# Peripherals.net
KiCad netlist of a schematic drawn in Altium Designer
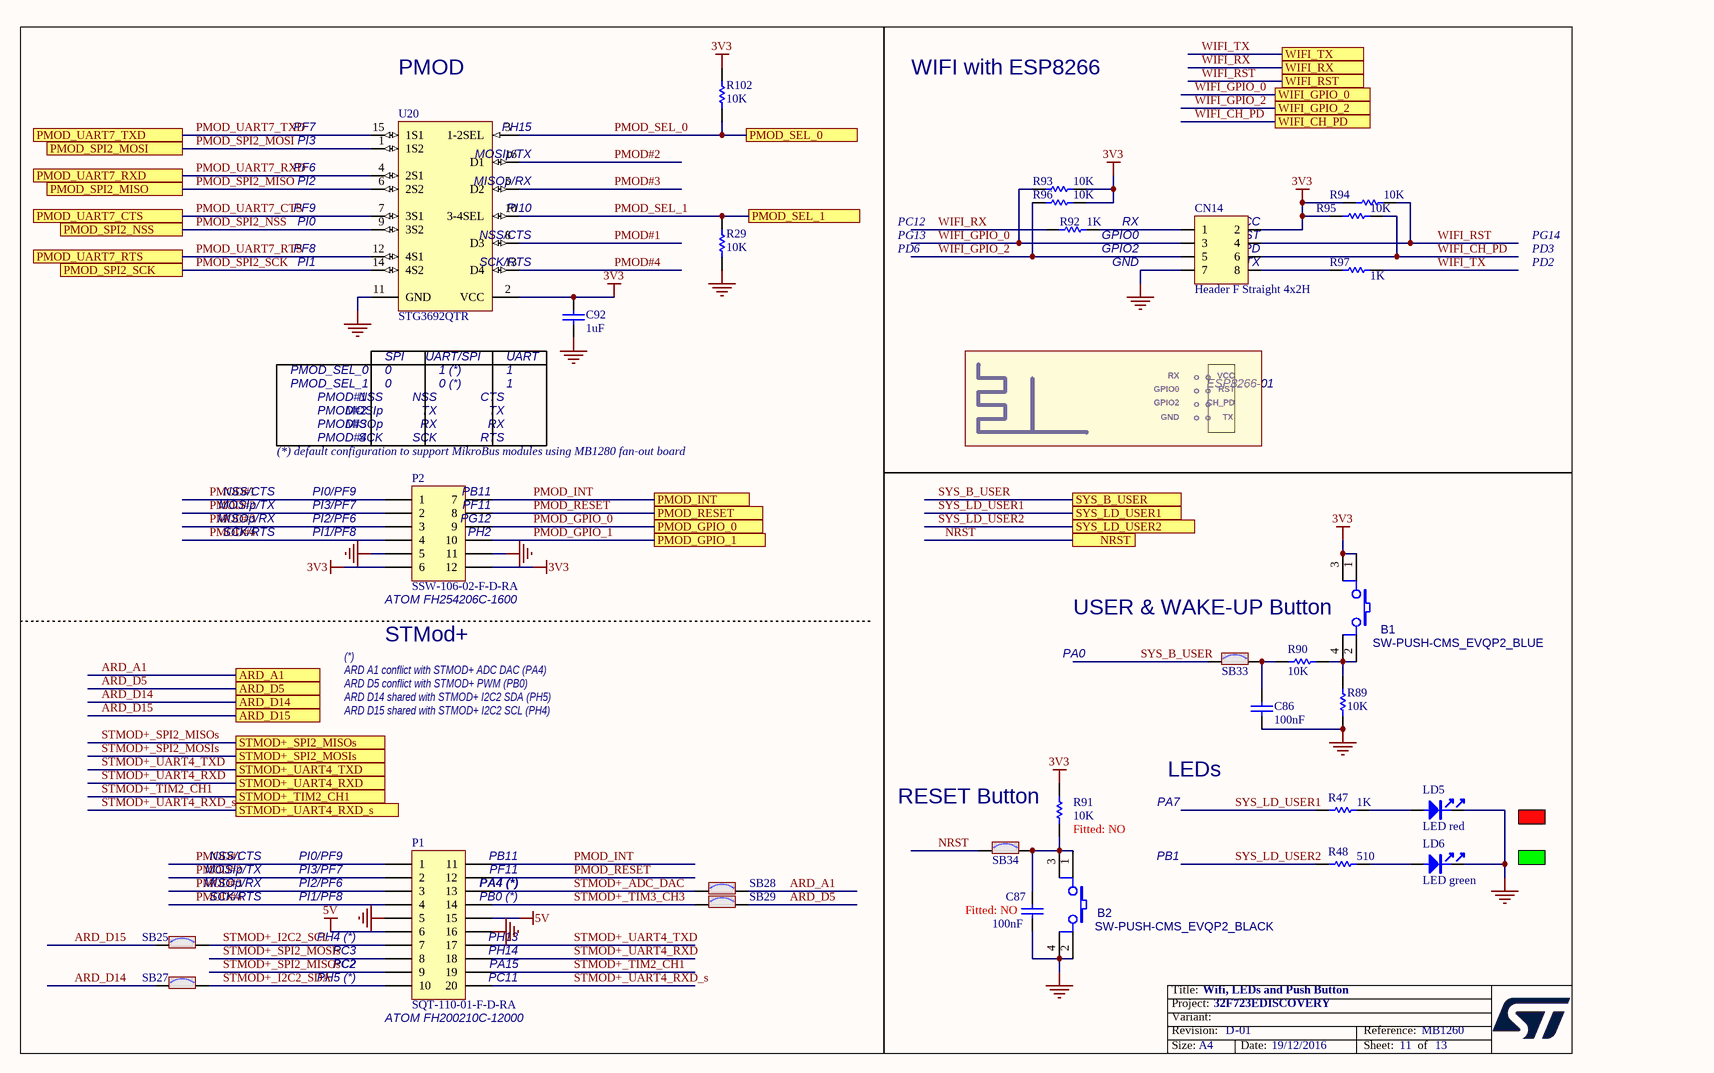
[diagram p0: Peripherals.SchDoc]

(export (version "E")
  (design (tool "Eeschema 10.0.6"))
  (components
    (comp (ref "B1")
      (value "SW-PUSH-CMS_EVQP2_BLUE")
      (footprint "TACT_4SM_3R5X5R5")
      (description "EVQP2 - 4.7mm x 3.5 mm SMD Light Touch Switch")
      (libsource (lib "MCD_TEMP_NPA") (part "SW-PUSH-CMS_EVQP2_BLUE"))
    )
    (comp (ref "B2")
      (value "SW-PUSH-CMS_EVQP2_BLACK")
      (footprint "TACT_4SM_3R5X5R5")
      (description "EVQP2 - 4.7mm x 3.5 mm SMD Light Touch Switch")
      (libsource (lib "MCD_TEMP_NPA") (part "SW-PUSH-CMS_EVQP2_BLACK"))
    )
    (comp (ref "C86")
      (value "100nF")
      (footprint "0402C")
      (description "Capacitor,100nF,16V,X7R,10%,0402,YAGEO")
      (libsource (lib "MCD_TOOLS") (part "Cap_100nF_X7R_10%_0402"))
    )
    (comp (ref "C87")
      (value "100nF")
      (footprint "0402C")
      (description "Capacitor,100nF,16V,X7R,10%,0402,YAGEO")
      (fields (field (name "FITTED") "NO"))
      (libsource (lib "MCD_TOOLS") (part "Cap_100nF_X7R_10%_0402"))
    )
    (comp (ref "C92")
      (value "1uF")
      (footprint "0603C")
      (description "Capacitor,1uF,16V,X5R,10%,0603,YAGEO")
      (libsource (lib "MCD_TOOLS_CAPACITOR") (part "Cap_1uF_X5R_10%_0603"))
    )
    (comp (ref "CN14")
      (value "Header F Straight 4x2H")
      (footprint "HDR_2X4_2R54")
      (description "Header Female, 4-Pin, Dual row, Straight")
      (libsource (lib "MCD_TOOLS_CONNECTOR") (part "Header 4X2F"))
    )
    (comp (ref "LD5")
      (value "LED red")
      (footprint "0603D")
      (description "LED red 0603")
      (libsource (lib "MCD_TEMP_NPA") (part "LED_red"))
    )
    (comp (ref "LD6")
      (value "LED green")
      (footprint "0603D")
      (description "LED green 0603")
      (libsource (lib "MCD_TEMP_NPA") (part "LED_green"))
    )
    (comp (ref "P1")
      (value "SQT-110-01-F-D-RA")
      (footprint "SQT-110-01-F-D-RA")
      (description "20 Position Receptacle Connector 0.079\" (2.00mm) Through Hole Right Angle")
      (libsource (lib "MCD_TEMP_NPA") (part "Header 10X2 TH RA 2mm"))
    )
    (comp (ref "P2")
      (value "SSW-106-02-F-D-RA")
      (footprint "SSW-106-02-F-D-RA")
      (description "12 Position Receptacle Connector 0.100\" (2.54mm) Through Hole Right Angle")
      (libsource (lib "MCD_TEMP_NPA") (part "Header 6X2 TH RA 2.54mm"))
    )
    (comp (ref "R29")
      (value "10K")
      (footprint "0402R")
      (description "Resistor,10K,0402,1%,YAGEO")
      (libsource (lib "MCD_TOOLS") (part "Res_10K_1%_0402"))
    )
    (comp (ref "R47")
      (value "1K")
      (footprint "0603R")
      (description "Resistor,1K,0603,1%,YAGEO")
      (fields (field (name "Comment") "1K_1%_0603"))
      (libsource (lib "MCD_TOOLS_RESISTOR") (part "Res_1K_1%_0603"))
    )
    (comp (ref "R48")
      (value "510")
      (footprint "0603R")
      (description "Resistor,510,0603,1%,YAGEO")
      (fields (field (name "Comment") "510_1%_0603"))
      (libsource (lib "MCD_TEMP_NPA") (part "Res_510_1%_0603"))
    )
    (comp (ref "R89")
      (value "10K")
      (footprint "0402R")
      (description "Resistor,10K,0402,1%,YAGEO")
      (libsource (lib "MCD_TOOLS") (part "Res_10K_1%_0402"))
    )
    (comp (ref "R90")
      (value "10K")
      (footprint "0402R")
      (description "Resistor,10K,0402,1%,YAGEO")
      (libsource (lib "MCD_TOOLS") (part "Res_10K_1%_0402"))
    )
    (comp (ref "R91")
      (value "10K")
      (footprint "0402R")
      (description "Resistor,10K,0402,1%,YAGEO")
      (fields (field (name "FITTED") "NO"))
      (libsource (lib "MCD_TOOLS") (part "Res_10K_1%_0402"))
    )
    (comp (ref "R92")
      (value "1K")
      (footprint "0402R")
      (description "Resistor,1K,0402,1%,YAGEO")
      (libsource (lib "MCD_TOOLS_RESISTOR") (part "Res_1K_1%_0402"))
    )
    (comp (ref "R93")
      (value "10K")
      (footprint "0402R")
      (description "Resistor,10K,0402,1%,YAGEO")
      (libsource (lib "MCD_TOOLS") (part "Res_10K_1%_0402"))
    )
    (comp (ref "R94")
      (value "10K")
      (footprint "0402R")
      (description "Resistor,10K,0402,1%,YAGEO")
      (libsource (lib "MCD_TOOLS") (part "Res_10K_1%_0402"))
    )
    (comp (ref "R95")
      (value "10K")
      (footprint "0402R")
      (description "Resistor,10K,0402,1%,YAGEO")
      (libsource (lib "MCD_TOOLS") (part "Res_10K_1%_0402"))
    )
    (comp (ref "R96")
      (value "10K")
      (footprint "0402R")
      (description "Resistor,10K,0402,1%,YAGEO")
      (libsource (lib "MCD_TOOLS") (part "Res_10K_1%_0402"))
    )
    (comp (ref "R97")
      (value "1K")
      (footprint "0402R")
      (description "Resistor,1K,0402,1%,YAGEO")
      (libsource (lib "MCD_TOOLS_RESISTOR") (part "Res_1K_1%_0402"))
    )
    (comp (ref "R102")
      (value "10K")
      (footprint "0402R")
      (description "Resistor,10K,0402,1%,YAGEO")
      (libsource (lib "MCD_TOOLS") (part "Res_10K_1%_0402"))
    )
    (comp (ref "SB25")
      (value "Solder Bridge ON")
      (footprint "JP2_SMD")
      (libsource (lib "MCD_TOOLS") (part "SB_ON"))
    )
    (comp (ref "SB27")
      (value "Solder Bridge ON")
      (footprint "JP2_SMD")
      (libsource (lib "MCD_TOOLS") (part "SB_ON"))
    )
    (comp (ref "SB28")
      (value "Solder Bridge ON")
      (footprint "JP2_SMD")
      (libsource (lib "MCD_TOOLS") (part "SB_ON"))
    )
    (comp (ref "SB29")
      (value "Solder Bridge ON")
      (footprint "JP2_SMD")
      (libsource (lib "MCD_TOOLS") (part "SB_ON"))
    )
    (comp (ref "SB33")
      (value "Solder Bridge ON")
      (footprint "JP2_SMD")
      (libsource (lib "MCD_TOOLS") (part "SB_ON"))
    )
    (comp (ref "SB34")
      (value "Solder Bridge ON")
      (footprint "JP2_SMD")
      (libsource (lib "MCD_TOOLS") (part "SB_ON"))
    )
    (comp (ref "U20")
      (value "STG3692QTR")
      (footprint "QFN16_0R4_2R5X1R7")
      (description "Low voltage high bandwidth quad SPDT switch")
      (libsource (lib "MCD_TEMP_NPA") (part "STG3692QTR"))
    )
  )
  (nets
    (net (code "1") (name "/ARD_A1") (class "Default")
      (node (ref "SB28") (pin "2") (pinfunction "2_2") (pintype "passive"))
    )
    (net (code "2") (name "/ARD_D5") (class "Default")
      (node (ref "SB29") (pin "2") (pinfunction "2_2") (pintype "passive"))
    )
    (net (code "3") (name "/ARD_D14") (class "Default")
      (node (ref "SB27") (pin "1") (pinfunction "1_1") (pintype "passive"))
    )
    (net (code "4") (name "/ARD_D15") (class "Default")
      (node (ref "SB25") (pin "1") (pinfunction "1_1") (pintype "passive"))
    )
    (net (code "5") (name "/NRST") (class "Default")
      (node (ref "SB34") (pin "1") (pinfunction "1_1") (pintype "passive"))
    )
    (net (code "6") (name "/PMOD#1") (class "Default")
      (node (ref "P1") (pin "1") (pinfunction "1_1") (pintype "passive"))
      (node (ref "P2") (pin "1") (pinfunction "1_1") (pintype "passive"))
      (node (ref "U20") (pin "8") (pinfunction "D3_8") (pintype "bidirectional"))
    )
    (net (code "7") (name "/PMOD#2") (class "Default")
      (node (ref "P1") (pin "2") (pinfunction "2_2") (pintype "passive"))
      (node (ref "P2") (pin "2") (pinfunction "2_2") (pintype "passive"))
      (node (ref "U20") (pin "16") (pinfunction "D1_16") (pintype "bidirectional"))
    )
    (net (code "8") (name "/PMOD#3") (class "Default")
      (node (ref "P1") (pin "3") (pinfunction "3_3") (pintype "passive"))
      (node (ref "P2") (pin "3") (pinfunction "3_3") (pintype "passive"))
      (node (ref "U20") (pin "5") (pinfunction "D2_5") (pintype "bidirectional"))
    )
    (net (code "9") (name "/PMOD#4") (class "Default")
      (node (ref "P1") (pin "4") (pinfunction "4_4") (pintype "passive"))
      (node (ref "P2") (pin "4") (pinfunction "4_4") (pintype "passive"))
      (node (ref "U20") (pin "13") (pinfunction "D4_13") (pintype "bidirectional"))
    )
    (net (code "10") (name "/PMOD_GPIO_0") (class "Default")
      (node (ref "P2") (pin "9") (pinfunction "9_9") (pintype "passive"))
    )
    (net (code "11") (name "/PMOD_GPIO_1") (class "Default")
      (node (ref "P2") (pin "10") (pinfunction "10_10") (pintype "passive"))
    )
    (net (code "12") (name "/PMOD_INT") (class "Default")
      (node (ref "P1") (pin "11") (pinfunction "11_11") (pintype "passive"))
      (node (ref "P2") (pin "7") (pinfunction "7_7") (pintype "passive"))
    )
    (net (code "13") (name "/PMOD_RESET") (class "Default")
      (node (ref "P1") (pin "12") (pinfunction "12_12") (pintype "passive"))
      (node (ref "P2") (pin "8") (pinfunction "8_8") (pintype "passive"))
    )
    (net (code "14") (name "/PMOD_SEL_0") (class "Default")
      (node (ref "R102") (pin "1") (pinfunction "1_1") (pintype "passive"))
      (node (ref "U20") (pin "3") (pinfunction "1-2SEL_3") (pintype "input"))
    )
    (net (code "15") (name "/PMOD_SEL_1") (class "Default")
      (node (ref "R29") (pin "2") (pinfunction "2_2") (pintype "passive"))
      (node (ref "U20") (pin "10") (pinfunction "3-4SEL_10") (pintype "bidirectional"))
    )
    (net (code "16") (name "/PMOD_SPI2_MISO") (class "Default")
      (node (ref "U20") (pin "6") (pinfunction "2S2_6") (pintype "bidirectional"))
    )
    (net (code "17") (name "/PMOD_SPI2_MOSI") (class "Default")
      (node (ref "U20") (pin "1") (pinfunction "1S2_1") (pintype "bidirectional"))
    )
    (net (code "18") (name "/PMOD_SPI2_NSS") (class "Default")
      (node (ref "U20") (pin "9") (pinfunction "3S2_9") (pintype "bidirectional"))
    )
    (net (code "19") (name "/PMOD_SPI2_SCK") (class "Default")
      (node (ref "U20") (pin "14") (pinfunction "4S2_14") (pintype "bidirectional"))
    )
    (net (code "20") (name "/PMOD_UART7_CTS") (class "Default")
      (node (ref "U20") (pin "7") (pinfunction "3S1_7") (pintype "bidirectional"))
    )
    (net (code "21") (name "/PMOD_UART7_RTS") (class "Default")
      (node (ref "U20") (pin "12") (pinfunction "4S1_12") (pintype "bidirectional"))
    )
    (net (code "22") (name "/PMOD_UART7_RXD") (class "Default")
      (node (ref "U20") (pin "4") (pinfunction "2S1_4") (pintype "bidirectional"))
    )
    (net (code "23") (name "/PMOD_UART7_TXD") (class "Default")
      (node (ref "U20") (pin "15") (pinfunction "1S1_15") (pintype "bidirectional"))
    )
    (net (code "24") (name "/STMOD+_ADC_DAC") (class "Default")
      (node (ref "P1") (pin "13") (pinfunction "13_13") (pintype "passive"))
      (node (ref "SB28") (pin "1") (pinfunction "1_1") (pintype "passive"))
    )
    (net (code "25") (name "/STMOD+_I2C2_SCL") (class "Default")
      (node (ref "P1") (pin "7") (pinfunction "7_7") (pintype "passive"))
      (node (ref "SB25") (pin "2") (pinfunction "2_2") (pintype "passive"))
    )
    (net (code "26") (name "/STMOD+_I2C2_SDA") (class "Default")
      (node (ref "P1") (pin "10") (pinfunction "10_10") (pintype "passive"))
      (node (ref "SB27") (pin "2") (pinfunction "2_2") (pintype "passive"))
    )
    (net (code "27") (name "/STMOD+_SPI2_MISOs") (class "Default")
      (node (ref "P1") (pin "9") (pinfunction "9_9") (pintype "passive"))
    )
    (net (code "28") (name "/STMOD+_SPI2_MOSIs") (class "Default")
      (node (ref "P1") (pin "8") (pinfunction "8_8") (pintype "passive"))
    )
    (net (code "29") (name "/STMOD+_TIM2_CH1") (class "Default")
      (node (ref "P1") (pin "19") (pinfunction "19_19") (pintype "passive"))
    )
    (net (code "30") (name "/STMOD+_TIM3_CH3") (class "Default")
      (node (ref "P1") (pin "14") (pinfunction "14_14") (pintype "passive"))
      (node (ref "SB29") (pin "1") (pinfunction "1_1") (pintype "passive"))
    )
    (net (code "31") (name "/STMOD+_UART4_RXD") (class "Default")
      (node (ref "P1") (pin "18") (pinfunction "18_18") (pintype "passive"))
    )
    (net (code "32") (name "/STMOD+_UART4_RXD_s") (class "Default")
      (node (ref "P1") (pin "20") (pinfunction "20_20") (pintype "passive"))
    )
    (net (code "33") (name "/STMOD+_UART4_TXD") (class "Default")
      (node (ref "P1") (pin "17") (pinfunction "17_17") (pintype "passive"))
    )
    (net (code "34") (name "/SYS_B_USER") (class "Default")
      (node (ref "SB33") (pin "1") (pinfunction "1_1") (pintype "passive"))
    )
    (net (code "35") (name "/SYS_LD_USER1") (class "Default")
      (node (ref "R47") (pin "1") (pinfunction "1_1") (pintype "passive"))
    )
    (net (code "36") (name "/SYS_LD_USER2") (class "Default")
      (node (ref "R48") (pin "1") (pinfunction "1_1") (pintype "passive"))
    )
    (net (code "37") (name "/WIFI_CH_PD") (class "Default")
      (node (ref "CN14") (pin "6") (pinfunction "6_6") (pintype "passive"))
      (node (ref "R95") (pin "2") (pinfunction "2_2") (pintype "passive"))
    )
    (net (code "38") (name "/WIFI_GPIO_0") (class "Default")
      (node (ref "CN14") (pin "3") (pinfunction "3_3") (pintype "passive"))
      (node (ref "R93") (pin "2") (pinfunction "2_2") (pintype "passive"))
    )
    (net (code "39") (name "/WIFI_GPIO_2") (class "Default")
      (node (ref "CN14") (pin "5") (pinfunction "5_5") (pintype "passive"))
      (node (ref "R96") (pin "2") (pinfunction "2_2") (pintype "passive"))
    )
    (net (code "40") (name "/WIFI_RST") (class "Default")
      (node (ref "CN14") (pin "4") (pinfunction "4_4") (pintype "passive"))
      (node (ref "R94") (pin "2") (pinfunction "2_2") (pintype "passive"))
    )
    (net (code "41") (name "/WIFI_RX") (class "Default")
      (node (ref "R92") (pin "1") (pinfunction "1_1") (pintype "passive"))
    )
    (net (code "42") (name "/WIFI_TX") (class "Default")
      (node (ref "R97") (pin "2") (pinfunction "2_2") (pintype "passive"))
    )
    (net (code "43") (name "3V3") (class "Default")
      (node (ref "B1") (pin "1") (pinfunction "1_1") (pintype "passive"))
      (node (ref "B1") (pin "3") (pinfunction "3_3") (pintype "passive"))
      (node (ref "C92") (pin "1") (pinfunction "1_1") (pintype "passive"))
      (node (ref "CN14") (pin "2") (pinfunction "2_2") (pintype "passive"))
      (node (ref "P2") (pin "12") (pinfunction "12_12") (pintype "passive"))
      (node (ref "P2") (pin "6") (pinfunction "6_6") (pintype "passive"))
      (node (ref "R102") (pin "2") (pinfunction "2_2") (pintype "passive"))
      (node (ref "R91") (pin "2") (pinfunction "2_2") (pintype "passive"))
      (node (ref "R93") (pin "1") (pinfunction "1_1") (pintype "passive"))
      (node (ref "R94") (pin "1") (pinfunction "1_1") (pintype "passive"))
      (node (ref "R95") (pin "1") (pinfunction "1_1") (pintype "passive"))
      (node (ref "R96") (pin "1") (pinfunction "1_1") (pintype "passive"))
      (node (ref "U20") (pin "2") (pinfunction "VCC_2") (pintype "power_in"))
    )
    (net (code "44") (name "5V") (class "Default")
      (node (ref "P1") (pin "15") (pinfunction "15_15") (pintype "passive"))
      (node (ref "P1") (pin "6") (pinfunction "6_6") (pintype "passive"))
    )
    (net (code "45") (name "GND") (class "Default")
      (node (ref "B2") (pin "2") (pinfunction "2_2") (pintype "passive"))
      (node (ref "B2") (pin "4") (pinfunction "4_4") (pintype "passive"))
      (node (ref "C86") (pin "1") (pinfunction "1_1") (pintype "passive"))
      (node (ref "C87") (pin "1") (pinfunction "1_1") (pintype "passive"))
      (node (ref "C92") (pin "2") (pinfunction "2_2") (pintype "passive"))
      (node (ref "CN14") (pin "7") (pinfunction "7_7") (pintype "passive"))
      (node (ref "LD5") (pin "2") (pintype "passive"))
      (node (ref "LD6") (pin "2") (pintype "passive"))
      (node (ref "P1") (pin "16") (pinfunction "16_16") (pintype "passive"))
      (node (ref "P1") (pin "5") (pinfunction "5_5") (pintype "passive"))
      (node (ref "P2") (pin "11") (pinfunction "11_11") (pintype "passive"))
      (node (ref "P2") (pin "5") (pinfunction "5_5") (pintype "passive"))
      (node (ref "R29") (pin "1") (pinfunction "1_1") (pintype "passive"))
      (node (ref "R89") (pin "1") (pinfunction "1_1") (pintype "passive"))
      (node (ref "U20") (pin "11") (pinfunction "GND_11") (pintype "power_in"))
    )
    (net (code "46") (name "Net-(B1-Pad2)") (class "Default")
      (node (ref "B1") (pin "2") (pinfunction "2_2") (pintype "passive"))
      (node (ref "B1") (pin "4") (pinfunction "4_4") (pintype "passive"))
      (node (ref "R89") (pin "2") (pinfunction "2_2") (pintype "passive"))
      (node (ref "R90") (pin "2") (pinfunction "2_2") (pintype "passive"))
    )
    (net (code "47") (name "Net-(B2-Pad1)") (class "Default")
      (node (ref "B2") (pin "1") (pinfunction "1_1") (pintype "passive"))
      (node (ref "B2") (pin "3") (pinfunction "3_3") (pintype "passive"))
      (node (ref "C87") (pin "2") (pinfunction "2_2") (pintype "passive"))
      (node (ref "R91") (pin "1") (pinfunction "1_1") (pintype "passive"))
      (node (ref "SB34") (pin "2") (pinfunction "2_2") (pintype "passive"))
    )
    (net (code "48") (name "Net-(C86-Pad2)") (class "Default")
      (node (ref "C86") (pin "2") (pinfunction "2_2") (pintype "passive"))
      (node (ref "R90") (pin "1") (pinfunction "1_1") (pintype "passive"))
      (node (ref "SB33") (pin "2") (pinfunction "2_2") (pintype "passive"))
    )
    (net (code "49") (name "Net-(CN14-Pad1)") (class "Default")
      (node (ref "CN14") (pin "1") (pinfunction "1_1") (pintype "passive"))
      (node (ref "R92") (pin "2") (pinfunction "2_2") (pintype "passive"))
    )
    (net (code "50") (name "Net-(CN14-Pad8)") (class "Default")
      (node (ref "CN14") (pin "8") (pinfunction "8_8") (pintype "passive"))
      (node (ref "R97") (pin "1") (pinfunction "1_1") (pintype "passive"))
    )
    (net (code "51") (name "Net-(LD5-Pad1)") (class "Default")
      (node (ref "LD5") (pin "1") (pintype "passive"))
      (node (ref "R47") (pin "2") (pinfunction "2_2") (pintype "passive"))
    )
    (net (code "52") (name "Net-(LD6-Pad1)") (class "Default")
      (node (ref "LD6") (pin "1") (pintype "passive"))
      (node (ref "R48") (pin "2") (pinfunction "2_2") (pintype "passive"))
    )
  )
)
